# LTC6811_Sheet.net
KiCad netlist of a schematic drawn in Altium Designer
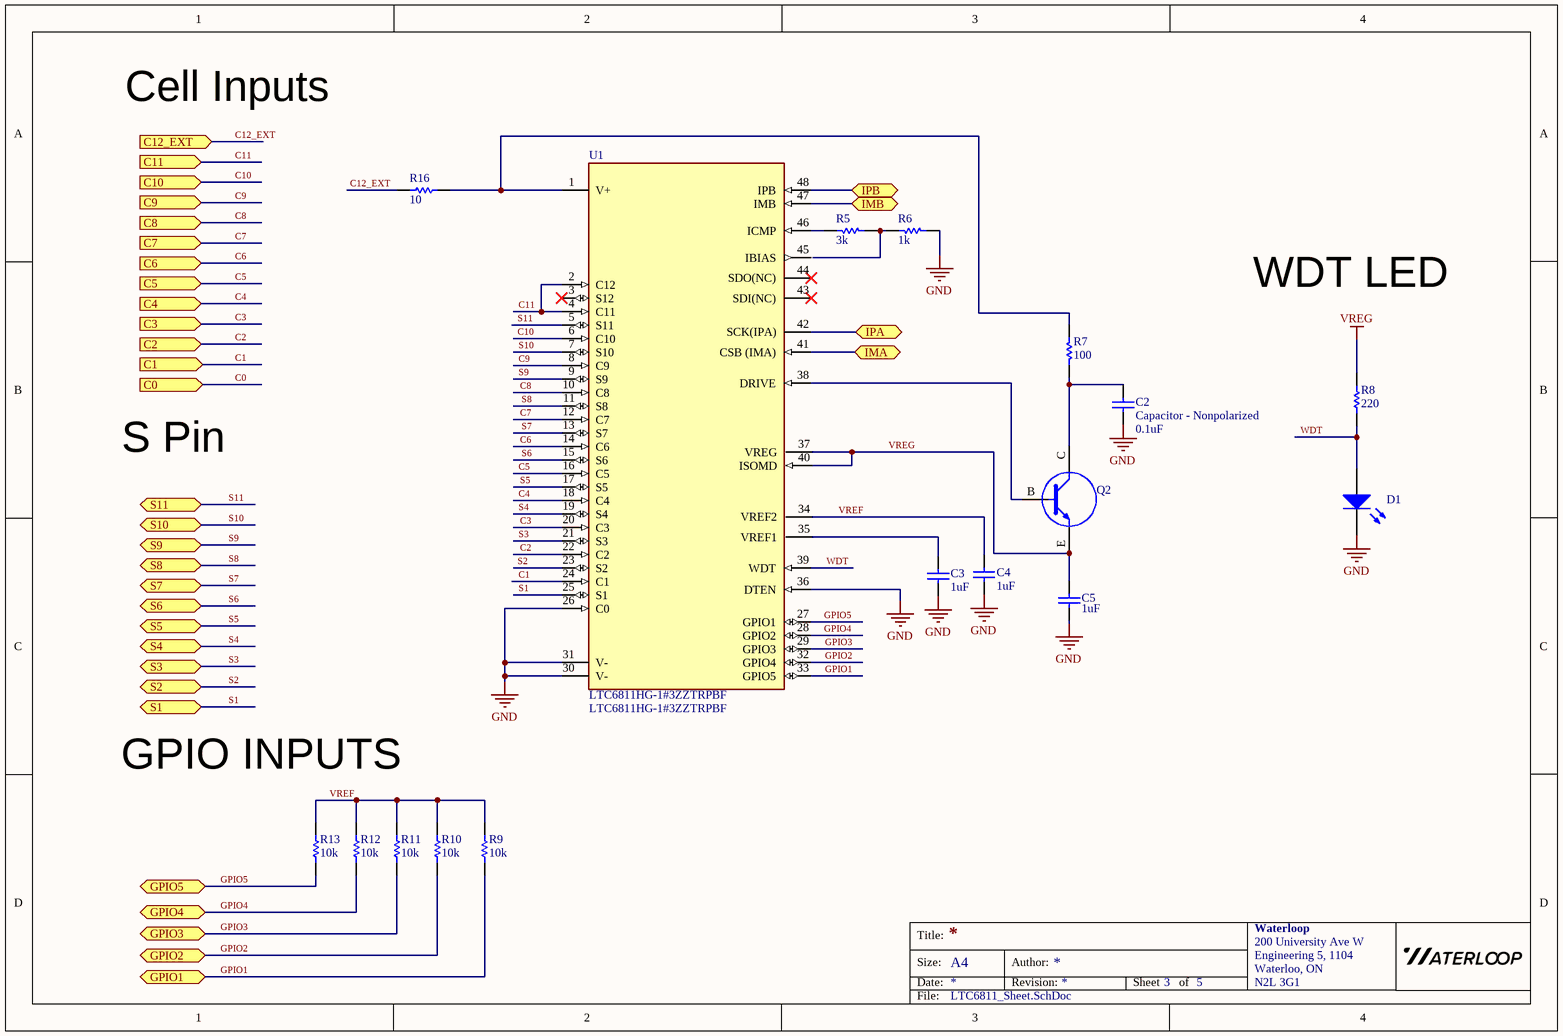
[diagram p0: LTC6811_Sheet.SchDoc]

(export (version "E")
  (design (tool "Eeschema 10.0.6"))
  (components
    (comp (ref "C2")
      (value "Capacitor - Nonpolarized")
      (footprint "0603 - Capacitor")
      (description "Nonpolarized Capacitor")
      (fields (field (name "ALTIUM_VALUE") "0.1uF"))
      (libsource (lib "General") (part "Capacitor - Nonpolarized"))
    )
    (comp (ref "C3")
      (value "1uF")
      (footprint "0603 - Capacitor")
      (description "Nonpolarized Capacitor")
      (fields (field (name "Comment") "Capacitor - Nonpolarized"))
      (libsource (lib "General") (part "Capacitor - Nonpolarized"))
    )
    (comp (ref "C4")
      (value "1uF")
      (footprint "0603 - Capacitor")
      (description "Nonpolarized Capacitor")
      (fields (field (name "Comment") "Capacitor - Nonpolarized"))
      (libsource (lib "General") (part "Capacitor - Nonpolarized"))
    )
    (comp (ref "C5")
      (value "1uF")
      (footprint "0603 - Capacitor")
      (description "Nonpolarized Capacitor")
      (fields (field (name "Comment") "Capacitor - Nonpolarized"))
      (libsource (lib "General") (part "Capacitor - Nonpolarized"))
    )
    (comp (ref "D1")
      (value "LED")
      (footprint "0805 - DIODE")
      (description "Light Emitting Diode")
      (libsource (lib "General") (part "LED"))
    )
    (comp (ref "Q2")
      (value "TRANS NPN 160V 0.6A POWERDI5")
      (footprint "DXT5551P5")
      (description "Bipolar (BJT) Transistor NPN 160 V 600 mA 130MHz 2.25 W Surface Mount PowerDI™ 5")
      (libsource (lib "GeneralComponents") (part "DXT5551P5-13"))
    )
    (comp (ref "R5")
      (value "3k")
      (footprint "0603 - Resistor")
      (description "Resistor")
      (libsource (lib "General") (part "Resistor"))
    )
    (comp (ref "R6")
      (value "1k")
      (footprint "0603 - Resistor")
      (description "Resistor")
      (libsource (lib "General") (part "Resistor"))
    )
    (comp (ref "R7")
      (value "100")
      (footprint "0603 - Resistor")
      (description "Resistor")
      (libsource (lib "General") (part "Resistor"))
    )
    (comp (ref "R8")
      (value "220")
      (footprint "0603 - Resistor")
      (description "Resistor")
      (libsource (lib "General") (part "Resistor"))
    )
    (comp (ref "R9")
      (value "10k")
      (footprint "0603 - Resistor")
      (description "Resistor")
      (libsource (lib "General") (part "Resistor"))
    )
    (comp (ref "R10")
      (value "10k")
      (footprint "0603 - Resistor")
      (description "Resistor")
      (libsource (lib "General") (part "Resistor"))
    )
    (comp (ref "R11")
      (value "10k")
      (footprint "0603 - Resistor")
      (description "Resistor")
      (libsource (lib "General") (part "Resistor"))
    )
    (comp (ref "R12")
      (value "10k")
      (footprint "0603 - Resistor")
      (description "Resistor")
      (libsource (lib "General") (part "Resistor"))
    )
    (comp (ref "R13")
      (value "10k")
      (footprint "0603 - Resistor")
      (description "Resistor")
      (libsource (lib "General") (part "Resistor"))
    )
    (comp (ref "R16")
      (value "10")
      (footprint "0603 - Resistor")
      (description "Resistor")
      (libsource (lib "General") (part "Resistor"))
    )
    (comp (ref "U1")
      (value "LTC6811HG-1#3ZZTRPBF")
      (footprint "LTC6811-1")
      (description "Multicell Battery Balancer 5.7V Automotive 48-Pin SSOP T/R")
      (fields
        (field (name "MANUFACTURER") "Analog Devices / Linear Technology")
        (field (name "MANUFACTURER PART NUMBER") "LTC6811HG-1#3ZZTRPBF")
      )
      (libsource (lib "BMS") (part "LTC6811HG-1#3ZZTRPBF"))
    )
  )
  (nets
    (net (code "2") (name "/C1") (class "Default")
      (node (ref "U1") (pin "24") (pinfunction "C1_24") (pintype "input"))
    )
    (net (code "3") (name "/C2") (class "Default")
      (node (ref "U1") (pin "22") (pinfunction "C2_22") (pintype "input"))
    )
    (net (code "4") (name "/C3") (class "Default")
      (node (ref "U1") (pin "20") (pinfunction "C3_20") (pintype "input"))
    )
    (net (code "5") (name "/C4") (class "Default")
      (node (ref "U1") (pin "18") (pinfunction "C4_18") (pintype "input"))
    )
    (net (code "6") (name "/C5") (class "Default")
      (node (ref "U1") (pin "16") (pinfunction "C5_16") (pintype "input"))
    )
    (net (code "7") (name "/C6") (class "Default")
      (node (ref "U1") (pin "14") (pinfunction "C6_14") (pintype "input"))
    )
    (net (code "8") (name "/C7") (class "Default")
      (node (ref "U1") (pin "12") (pinfunction "C7_12") (pintype "input"))
    )
    (net (code "9") (name "/C8") (class "Default")
      (node (ref "U1") (pin "10") (pinfunction "C8_10") (pintype "input"))
    )
    (net (code "10") (name "/C9") (class "Default")
      (node (ref "U1") (pin "8") (pinfunction "C9_8") (pintype "input"))
    )
    (net (code "11") (name "/C10") (class "Default")
      (node (ref "U1") (pin "6") (pinfunction "C10_6") (pintype "input"))
    )
    (net (code "12") (name "/C11") (class "Default")
      (node (ref "U1") (pin "2") (pinfunction "C12_2") (pintype "input"))
      (node (ref "U1") (pin "4") (pinfunction "C11_4") (pintype "input"))
    )
    (net (code "13") (name "/C12_EXT") (class "Default")
      (node (ref "R16") (pin "1") (pinfunction "1_1") (pintype "passive"))
    )
    (net (code "14") (name "/GPIO1") (class "Default")
      (node (ref "R9") (pin "1") (pinfunction "1_1") (pintype "passive"))
      (node (ref "U1") (pin "33") (pinfunction "GPIO5_33") (pintype "bidirectional"))
    )
    (net (code "15") (name "/GPIO2") (class "Default")
      (node (ref "R10") (pin "1") (pinfunction "1_1") (pintype "passive"))
      (node (ref "U1") (pin "32") (pinfunction "GPIO4_32") (pintype "bidirectional"))
    )
    (net (code "16") (name "/GPIO3") (class "Default")
      (node (ref "R11") (pin "1") (pinfunction "1_1") (pintype "passive"))
      (node (ref "U1") (pin "29") (pinfunction "GPIO3_29") (pintype "bidirectional"))
    )
    (net (code "17") (name "/GPIO4") (class "Default")
      (node (ref "R12") (pin "1") (pinfunction "1_1") (pintype "passive"))
      (node (ref "U1") (pin "28") (pinfunction "GPIO2_28") (pintype "bidirectional"))
    )
    (net (code "18") (name "/GPIO5") (class "Default")
      (node (ref "R13") (pin "1") (pinfunction "1_1") (pintype "passive"))
      (node (ref "U1") (pin "27") (pinfunction "GPIO1_27") (pintype "bidirectional"))
    )
    (net (code "19") (name "/IMA") (class "Default")
      (node (ref "U1") (pin "41") (pinfunction "CSB_(IMA)_41") (pintype "input"))
    )
    (net (code "20") (name "/IMB") (class "Default")
      (node (ref "U1") (pin "47") (pinfunction "IMB_47") (pintype "input"))
    )
    (net (code "21") (name "/IPA") (class "Default")
      (node (ref "U1") (pin "42") (pinfunction "SCK(IPA)_42") (pintype "passive"))
    )
    (net (code "22") (name "/IPB") (class "Default")
      (node (ref "U1") (pin "48") (pinfunction "IPB_48") (pintype "input"))
    )
    (net (code "23") (name "/S1") (class "Default")
      (node (ref "U1") (pin "25") (pinfunction "S1_25") (pintype "bidirectional"))
    )
    (net (code "24") (name "/S2") (class "Default")
      (node (ref "U1") (pin "23") (pinfunction "S2_23") (pintype "bidirectional"))
    )
    (net (code "25") (name "/S3") (class "Default")
      (node (ref "U1") (pin "21") (pinfunction "S3_21") (pintype "bidirectional"))
    )
    (net (code "26") (name "/S4") (class "Default")
      (node (ref "U1") (pin "19") (pinfunction "S4_19") (pintype "bidirectional"))
    )
    (net (code "27") (name "/S5") (class "Default")
      (node (ref "U1") (pin "17") (pinfunction "S5_17") (pintype "bidirectional"))
    )
    (net (code "28") (name "/S6") (class "Default")
      (node (ref "U1") (pin "15") (pinfunction "S6_15") (pintype "bidirectional"))
    )
    (net (code "29") (name "/S7") (class "Default")
      (node (ref "U1") (pin "13") (pinfunction "S7_13") (pintype "bidirectional"))
    )
    (net (code "30") (name "/S8") (class "Default")
      (node (ref "U1") (pin "11") (pinfunction "S8_11") (pintype "bidirectional"))
    )
    (net (code "31") (name "/S9") (class "Default")
      (node (ref "U1") (pin "9") (pinfunction "S9_9") (pintype "bidirectional"))
    )
    (net (code "32") (name "/S10") (class "Default")
      (node (ref "U1") (pin "7") (pinfunction "S10_7") (pintype "bidirectional"))
    )
    (net (code "33") (name "/S11") (class "Default")
      (node (ref "U1") (pin "5") (pinfunction "S11_5") (pintype "bidirectional"))
    )
    (net (code "34") (name "/VREF") (class "Default")
      (node (ref "C4") (pin "2") (pinfunction "2_2") (pintype "passive"))
      (node (ref "R10") (pin "2") (pinfunction "2_2") (pintype "passive"))
      (node (ref "R11") (pin "2") (pinfunction "2_2") (pintype "passive"))
      (node (ref "R12") (pin "2") (pinfunction "2_2") (pintype "passive"))
      (node (ref "R13") (pin "2") (pinfunction "2_2") (pintype "passive"))
      (node (ref "R9") (pin "2") (pinfunction "2_2") (pintype "passive"))
      (node (ref "U1") (pin "34") (pinfunction "VREF2_34") (pintype "power_in"))
    )
    (net (code "35") (name "/WDT") (class "Default")
      (node (ref "D1") (pin "1") (pinfunction "A_1") (pintype "passive"))
      (node (ref "R8") (pin "1") (pinfunction "1_1") (pintype "passive"))
      (node (ref "U1") (pin "39") (pinfunction "WDT_39") (pintype "input"))
    )
    (net (code "36") (name "GND") (class "Default")
      (node (ref "C2") (pin "1") (pinfunction "1_1") (pintype "passive"))
      (node (ref "C3") (pin "1") (pinfunction "1_1") (pintype "passive"))
      (node (ref "C4") (pin "1") (pinfunction "1_1") (pintype "passive"))
      (node (ref "C5") (pin "1") (pinfunction "1_1") (pintype "passive"))
      (node (ref "D1") (pin "2") (pinfunction "K_2") (pintype "passive"))
      (node (ref "R6") (pin "1") (pinfunction "1_1") (pintype "passive"))
      (node (ref "U1") (pin "26") (pinfunction "C0_26") (pintype "input"))
      (node (ref "U1") (pin "30") (pinfunction "V-_30") (pintype "power_in"))
      (node (ref "U1") (pin "31") (pinfunction "V-_31") (pintype "power_in"))
      (node (ref "U1") (pin "36") (pinfunction "DTEN_36") (pintype "input"))
    )
    (net (code "37") (name "Net-(Q2-1)") (class "Default")
      (node (ref "C2") (pin "2") (pinfunction "2_2") (pintype "passive"))
      (node (ref "Q2") (pin "C") (pinfunction "1_C") (pintype "passive"))
      (node (ref "R7") (pin "2") (pinfunction "2_2") (pintype "passive"))
    )
    (net (code "38") (name "Net-(Q2-2)") (class "Default")
      (node (ref "Q2") (pin "B") (pinfunction "2_B") (pintype "passive"))
      (node (ref "U1") (pin "38") (pinfunction "DRIVE_38") (pintype "input"))
    )
    (net (code "39") (name "Net-(R5-Pad1)") (class "Default")
      (node (ref "R5") (pin "1") (pinfunction "1_1") (pintype "passive"))
      (node (ref "R6") (pin "2") (pinfunction "2_2") (pintype "passive"))
    )
    (net (code "40") (name "Net-(U1-ICMP)") (class "Default")
      (node (ref "R5") (pin "2") (pinfunction "2_2") (pintype "passive"))
      (node (ref "U1") (pin "46") (pinfunction "ICMP_46") (pintype "input"))
    )
    (net (code "41") (name "Net-(U1-V+)") (class "Default")
      (node (ref "R16") (pin "2") (pinfunction "2_2") (pintype "passive"))
      (node (ref "R7") (pin "1") (pinfunction "1_1") (pintype "passive"))
      (node (ref "U1") (pin "1") (pinfunction "V+_1") (pintype "power_in"))
    )
    (net (code "42") (name "Net-(U1-VREF1)") (class "Default")
      (node (ref "C3") (pin "2") (pinfunction "2_2") (pintype "passive"))
      (node (ref "U1") (pin "35") (pinfunction "VREF1_35") (pintype "power_in"))
    )
    (net (code "43") (name "VREG") (class "Default")
      (node (ref "C5") (pin "2") (pinfunction "2_2") (pintype "passive"))
      (node (ref "Q2") (pin "E") (pinfunction "3_E") (pintype "passive"))
      (node (ref "R8") (pin "2") (pinfunction "2_2") (pintype "passive"))
      (node (ref "U1") (pin "37") (pinfunction "VREG_37") (pintype "power_in"))
      (node (ref "U1") (pin "40") (pinfunction "ISOMD_40") (pintype "input"))
    )
    (net (code "44") (name "unconnected-(U1-IBIAS-Pad45)") (class "Default")
      (node (ref "U1") (pin "45") (pinfunction "IBIAS_45") (pintype "output"))
    )
    (net (code "45") (name "unconnected-(U1-S12-Pad3)") (class "Default")
      (node (ref "U1") (pin "3") (pinfunction "S12_3") (pintype "bidirectional+no_connect"))
    )
    (net (code "46") (name "unconnected-(U1-SDI(NC)-Pad43)") (class "Default")
      (node (ref "U1") (pin "43") (pinfunction "SDI(NC)_43") (pintype "passive+no_connect"))
    )
    (net (code "47") (name "unconnected-(U1-SDO(NC)-Pad44)") (class "Default")
      (node (ref "U1") (pin "44") (pinfunction "SDO(NC)_44") (pintype "passive+no_connect"))
    )
  )
)
